# keypad.net
KiCad netlist of a schematic drawn in Altium Designer
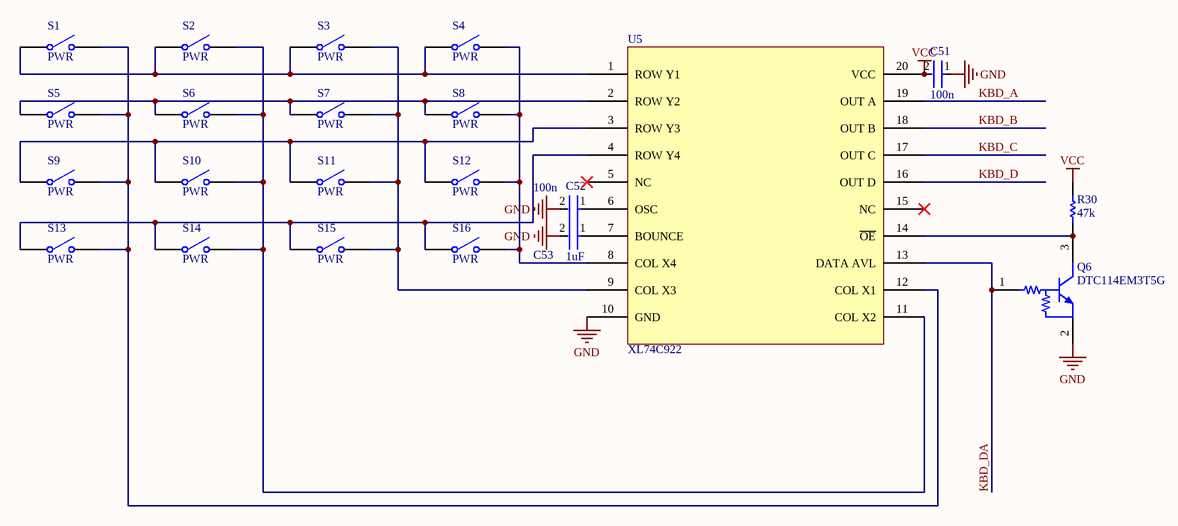
[diagram p0: keypad.SchDoc]

(export (version "E")
  (design (tool "Eeschema 10.0.6"))
  (components
    (comp (ref "C51")
      (value "100n")
      (footprint "FP-GRM155-0_05-IPC_A")
      (description "Chip Multilayer Ceramic Capacitors for General Purpose, 0402, 470pF, C0G, 30ppm/°C, 5%, 50V")
      (fields (field (name "VOLTAGE") "50V") (field (name "TOLERANCE") "5%"))
      (libsource (lib "Altium Content Vault") (part "02cd4be3c70576c341d710602a673aa"))
    )
    (comp (ref "C52")
      (value "100n")
      (footprint "FP-GRM188-0_1-e0_2_0_55-IPC_A")
      (description "Chip Multilayer Ceramic Capacitors for General Purpose, 0603, 10uF, X5R, 15%, 20%, 6.3V")
      (fields (field (name "VOLTAGE") "6.3V") (field (name "TOLERANCE") "20%"))
      (libsource (lib "Altium Content Vault") (part "02cd4be3c70576c341d710602a673aa"))
    )
    (comp (ref "C53")
      (value "1uF")
      (footprint "FP-GRM188-0_1-e0_2_0_55-IPC_A")
      (description "Chip Multilayer Ceramic Capacitors for General Purpose, 0603, 10uF, X5R, 15%, 20%, 6.3V")
      (fields (field (name "VOLTAGE") "6.3V") (field (name "TOLERANCE") "20%"))
      (libsource (lib "Altium Content Vault") (part "02cd4be3c70576c341d710602a673aa"))
    )
    (comp (ref "Q6")
      (value "DTC114EM3T5G")
      (footprint "ONSC-SOT-723-3-631AA-01_V")
      (fields (field (name "MANUFACTURER") "On Semiconductor"))
      (libsource (lib "Altium Content Vault") (part "ONSC-BRT-NPN-B1E2C3-3"))
    )
    (comp (ref "R30")
      (value "47k")
      (footprint "RESC1005X40X25NL05T10")
      (fields (field (name "MANUFACTURER") "Yageo / Phycomp") (field (name "PART NUMBER") "RC0402JR-070RL"))
      (libsource (lib "Altium Content Vault") (part "RES"))
    )
    (comp (ref "S1")
      (value "PWR")
      (footprint "3-6-2.5")
      (description "Single-Pole, Single-Throw Switch")
      (fields (field (name "PUBLISHER") "Altium Limited"))
      (libsource (lib "Miscellaneous Devices") (part "SW-SPST"))
    )
    (comp (ref "S2")
      (value "PWR")
      (footprint "3-6-2.5")
      (description "Single-Pole, Single-Throw Switch")
      (fields (field (name "PUBLISHER") "Altium Limited"))
      (libsource (lib "Miscellaneous Devices") (part "SW-SPST"))
    )
    (comp (ref "S3")
      (value "PWR")
      (footprint "3-6-2.5")
      (description "Single-Pole, Single-Throw Switch")
      (fields (field (name "PUBLISHER") "Altium Limited"))
      (libsource (lib "Miscellaneous Devices") (part "SW-SPST"))
    )
    (comp (ref "S4")
      (value "PWR")
      (footprint "3-6-2.5")
      (description "Single-Pole, Single-Throw Switch")
      (fields (field (name "PUBLISHER") "Altium Limited"))
      (libsource (lib "Miscellaneous Devices") (part "SW-SPST"))
    )
    (comp (ref "S5")
      (value "PWR")
      (footprint "3-6-2.5")
      (description "Single-Pole, Single-Throw Switch")
      (fields (field (name "PUBLISHER") "Altium Limited"))
      (libsource (lib "Miscellaneous Devices") (part "SW-SPST"))
    )
    (comp (ref "S6")
      (value "PWR")
      (footprint "3-6-2.5")
      (description "Single-Pole, Single-Throw Switch")
      (fields (field (name "PUBLISHER") "Altium Limited"))
      (libsource (lib "Miscellaneous Devices") (part "SW-SPST"))
    )
    (comp (ref "S7")
      (value "PWR")
      (footprint "3-6-2.5")
      (description "Single-Pole, Single-Throw Switch")
      (fields (field (name "PUBLISHER") "Altium Limited"))
      (libsource (lib "Miscellaneous Devices") (part "SW-SPST"))
    )
    (comp (ref "S8")
      (value "PWR")
      (footprint "3-6-2.5")
      (description "Single-Pole, Single-Throw Switch")
      (fields (field (name "PUBLISHER") "Altium Limited"))
      (libsource (lib "Miscellaneous Devices") (part "SW-SPST"))
    )
    (comp (ref "S9")
      (value "PWR")
      (footprint "3-6-2.5")
      (description "Single-Pole, Single-Throw Switch")
      (fields (field (name "PUBLISHER") "Altium Limited"))
      (libsource (lib "Miscellaneous Devices") (part "SW-SPST"))
    )
    (comp (ref "S10")
      (value "PWR")
      (footprint "3-6-2.5")
      (description "Single-Pole, Single-Throw Switch")
      (fields (field (name "PUBLISHER") "Altium Limited"))
      (libsource (lib "Miscellaneous Devices") (part "SW-SPST"))
    )
    (comp (ref "S11")
      (value "PWR")
      (footprint "3-6-2.5")
      (description "Single-Pole, Single-Throw Switch")
      (fields (field (name "PUBLISHER") "Altium Limited"))
      (libsource (lib "Miscellaneous Devices") (part "SW-SPST"))
    )
    (comp (ref "S12")
      (value "PWR")
      (footprint "3-6-2.5")
      (description "Single-Pole, Single-Throw Switch")
      (fields (field (name "PUBLISHER") "Altium Limited"))
      (libsource (lib "Miscellaneous Devices") (part "SW-SPST"))
    )
    (comp (ref "S13")
      (value "PWR")
      (footprint "3-6-2.5")
      (description "Single-Pole, Single-Throw Switch")
      (fields (field (name "PUBLISHER") "Altium Limited"))
      (libsource (lib "Miscellaneous Devices") (part "SW-SPST"))
    )
    (comp (ref "S14")
      (value "PWR")
      (footprint "3-6-2.5")
      (description "Single-Pole, Single-Throw Switch")
      (fields (field (name "PUBLISHER") "Altium Limited"))
      (libsource (lib "Miscellaneous Devices") (part "SW-SPST"))
    )
    (comp (ref "S15")
      (value "PWR")
      (footprint "3-6-2.5")
      (description "Single-Pole, Single-Throw Switch")
      (fields (field (name "PUBLISHER") "Altium Limited"))
      (libsource (lib "Miscellaneous Devices") (part "SW-SPST"))
    )
    (comp (ref "S16")
      (value "PWR")
      (footprint "3-6-2.5")
      (description "Single-Pole, Single-Throw Switch")
      (fields (field (name "PUBLISHER") "Altium Limited"))
      (libsource (lib "Miscellaneous Devices") (part "SW-SPST"))
    )
    (comp (ref "U5") (value "XL74C922") (footprint "XL74C922") (libsource (lib "XL74C922") (part "XL74C922")))
  )
  (nets
    (net (code "1") (name "/KBD_A") (class "Default")
      (node (ref "U5") (pin "19") (pinfunction "OUT_A_19") (pintype "passive"))
    )
    (net (code "2") (name "/KBD_B") (class "Default")
      (node (ref "U5") (pin "18") (pinfunction "OUT_B_18") (pintype "passive"))
    )
    (net (code "3") (name "/KBD_C") (class "Default")
      (node (ref "U5") (pin "17") (pinfunction "OUT_C_17") (pintype "passive"))
    )
    (net (code "4") (name "/KBD_D") (class "Default")
      (node (ref "U5") (pin "16") (pinfunction "OUT_D_16") (pintype "passive"))
    )
    (net (code "5") (name "/KBD_DA") (class "Default")
      (node (ref "Q6") (pin "1") (pinfunction "B_1") (pintype "passive"))
      (node (ref "U5") (pin "13") (pinfunction "DATA_AVL_13") (pintype "passive"))
    )
    (net (code "6") (name "GND") (class "Default")
      (node (ref "C51") (pin "1") (pinfunction "1_1") (pintype "passive"))
      (node (ref "C52") (pin "2") (pinfunction "2_2") (pintype "passive"))
      (node (ref "C53") (pin "2") (pinfunction "2_2") (pintype "passive"))
      (node (ref "Q6") (pin "2") (pinfunction "E_2") (pintype "passive"))
      (node (ref "U5") (pin "10") (pinfunction "GND_10") (pintype "passive"))
    )
    (net (code "7") (name "Net-(Q6-C)") (class "Default")
      (node (ref "Q6") (pin "3") (pinfunction "C_3") (pintype "passive"))
      (node (ref "R30") (pin "1") (pinfunction "1_1") (pintype "passive"))
      (node (ref "U5") (pin "14") (pinfunction "~{OE}_14") (pintype "passive"))
    )
    (net (code "8") (name "Net-(S1-COMMON)") (class "Default")
      (node (ref "S1") (pin "1") (pinfunction "COMMON_1") (pintype "passive"))
      (node (ref "S2") (pin "1") (pinfunction "COMMON_1") (pintype "passive"))
      (node (ref "S3") (pin "1") (pinfunction "COMMON_1") (pintype "passive"))
      (node (ref "S4") (pin "1") (pinfunction "COMMON_1") (pintype "passive"))
      (node (ref "U5") (pin "1") (pinfunction "ROW_Y1_1") (pintype "passive"))
    )
    (net (code "9") (name "Net-(S1-NO)") (class "Default")
      (node (ref "S1") (pin "2") (pinfunction "NO_2") (pintype "passive"))
      (node (ref "S13") (pin "2") (pinfunction "NO_2") (pintype "passive"))
      (node (ref "S5") (pin "2") (pinfunction "NO_2") (pintype "passive"))
      (node (ref "S9") (pin "2") (pinfunction "NO_2") (pintype "passive"))
      (node (ref "U5") (pin "12") (pinfunction "COL_X1_12") (pintype "passive"))
    )
    (net (code "10") (name "Net-(S5-COMMON)") (class "Default")
      (node (ref "S5") (pin "1") (pinfunction "COMMON_1") (pintype "passive"))
      (node (ref "S6") (pin "1") (pinfunction "COMMON_1") (pintype "passive"))
      (node (ref "S7") (pin "1") (pinfunction "COMMON_1") (pintype "passive"))
      (node (ref "S8") (pin "1") (pinfunction "COMMON_1") (pintype "passive"))
      (node (ref "U5") (pin "2") (pinfunction "ROW_Y2_2") (pintype "passive"))
    )
    (net (code "11") (name "Net-(S10-COMMON)") (class "Default")
      (node (ref "S10") (pin "1") (pinfunction "COMMON_1") (pintype "passive"))
      (node (ref "S11") (pin "1") (pinfunction "COMMON_1") (pintype "passive"))
      (node (ref "S12") (pin "1") (pinfunction "COMMON_1") (pintype "passive"))
      (node (ref "S9") (pin "1") (pinfunction "COMMON_1") (pintype "passive"))
      (node (ref "U5") (pin "3") (pinfunction "ROW_Y3_3") (pintype "passive"))
    )
    (net (code "12") (name "Net-(S10-NO)") (class "Default")
      (node (ref "S10") (pin "2") (pinfunction "NO_2") (pintype "passive"))
      (node (ref "S14") (pin "2") (pinfunction "NO_2") (pintype "passive"))
      (node (ref "S2") (pin "2") (pinfunction "NO_2") (pintype "passive"))
      (node (ref "S6") (pin "2") (pinfunction "NO_2") (pintype "passive"))
      (node (ref "U5") (pin "11") (pinfunction "COL_X2_11") (pintype "passive"))
    )
    (net (code "13") (name "Net-(S11-NO)") (class "Default")
      (node (ref "S11") (pin "2") (pinfunction "NO_2") (pintype "passive"))
      (node (ref "S15") (pin "2") (pinfunction "NO_2") (pintype "passive"))
      (node (ref "S3") (pin "2") (pinfunction "NO_2") (pintype "passive"))
      (node (ref "S7") (pin "2") (pinfunction "NO_2") (pintype "passive"))
      (node (ref "U5") (pin "9") (pinfunction "COL_X3_9") (pintype "passive"))
    )
    (net (code "14") (name "Net-(S12-NO)") (class "Default")
      (node (ref "S12") (pin "2") (pinfunction "NO_2") (pintype "passive"))
      (node (ref "S16") (pin "2") (pinfunction "NO_2") (pintype "passive"))
      (node (ref "S4") (pin "2") (pinfunction "NO_2") (pintype "passive"))
      (node (ref "S8") (pin "2") (pinfunction "NO_2") (pintype "passive"))
      (node (ref "U5") (pin "8") (pinfunction "COL_X4_8") (pintype "passive"))
    )
    (net (code "15") (name "Net-(S13-COMMON)") (class "Default")
      (node (ref "S13") (pin "1") (pinfunction "COMMON_1") (pintype "passive"))
      (node (ref "S14") (pin "1") (pinfunction "COMMON_1") (pintype "passive"))
      (node (ref "S15") (pin "1") (pinfunction "COMMON_1") (pintype "passive"))
      (node (ref "S16") (pin "1") (pinfunction "COMMON_1") (pintype "passive"))
      (node (ref "U5") (pin "4") (pinfunction "ROW_Y4_4") (pintype "passive"))
    )
    (net (code "16") (name "Net-(U5-BOUNCE)") (class "Default")
      (node (ref "C53") (pin "1") (pinfunction "1_1") (pintype "passive"))
      (node (ref "U5") (pin "7") (pinfunction "BOUNCE_7") (pintype "passive"))
    )
    (net (code "17") (name "Net-(U5-OSC)") (class "Default")
      (node (ref "C52") (pin "1") (pinfunction "1_1") (pintype "passive"))
      (node (ref "U5") (pin "6") (pinfunction "OSC_6") (pintype "passive"))
    )
    (net (code "18") (name "VCC") (class "Default")
      (node (ref "C51") (pin "2") (pinfunction "2_2") (pintype "passive"))
      (node (ref "R30") (pin "2") (pinfunction "2_2") (pintype "passive"))
      (node (ref "U5") (pin "20") (pinfunction "VCC_20") (pintype "passive"))
    )
    (net (code "19") (name "unconnected-(U5-NC-Pad5)") (class "Default")
      (node (ref "U5") (pin "5") (pinfunction "NC_5") (pintype "passive+no_connect"))
    )
    (net (code "20") (name "unconnected-(U5-NC-Pad15)") (class "Default")
      (node (ref "U5") (pin "15") (pinfunction "NC_15") (pintype "passive+no_connect"))
    )
  )
)
